# RFID_Sheet_1.net
KiCad netlist of a schematic drawn in Altium Designer
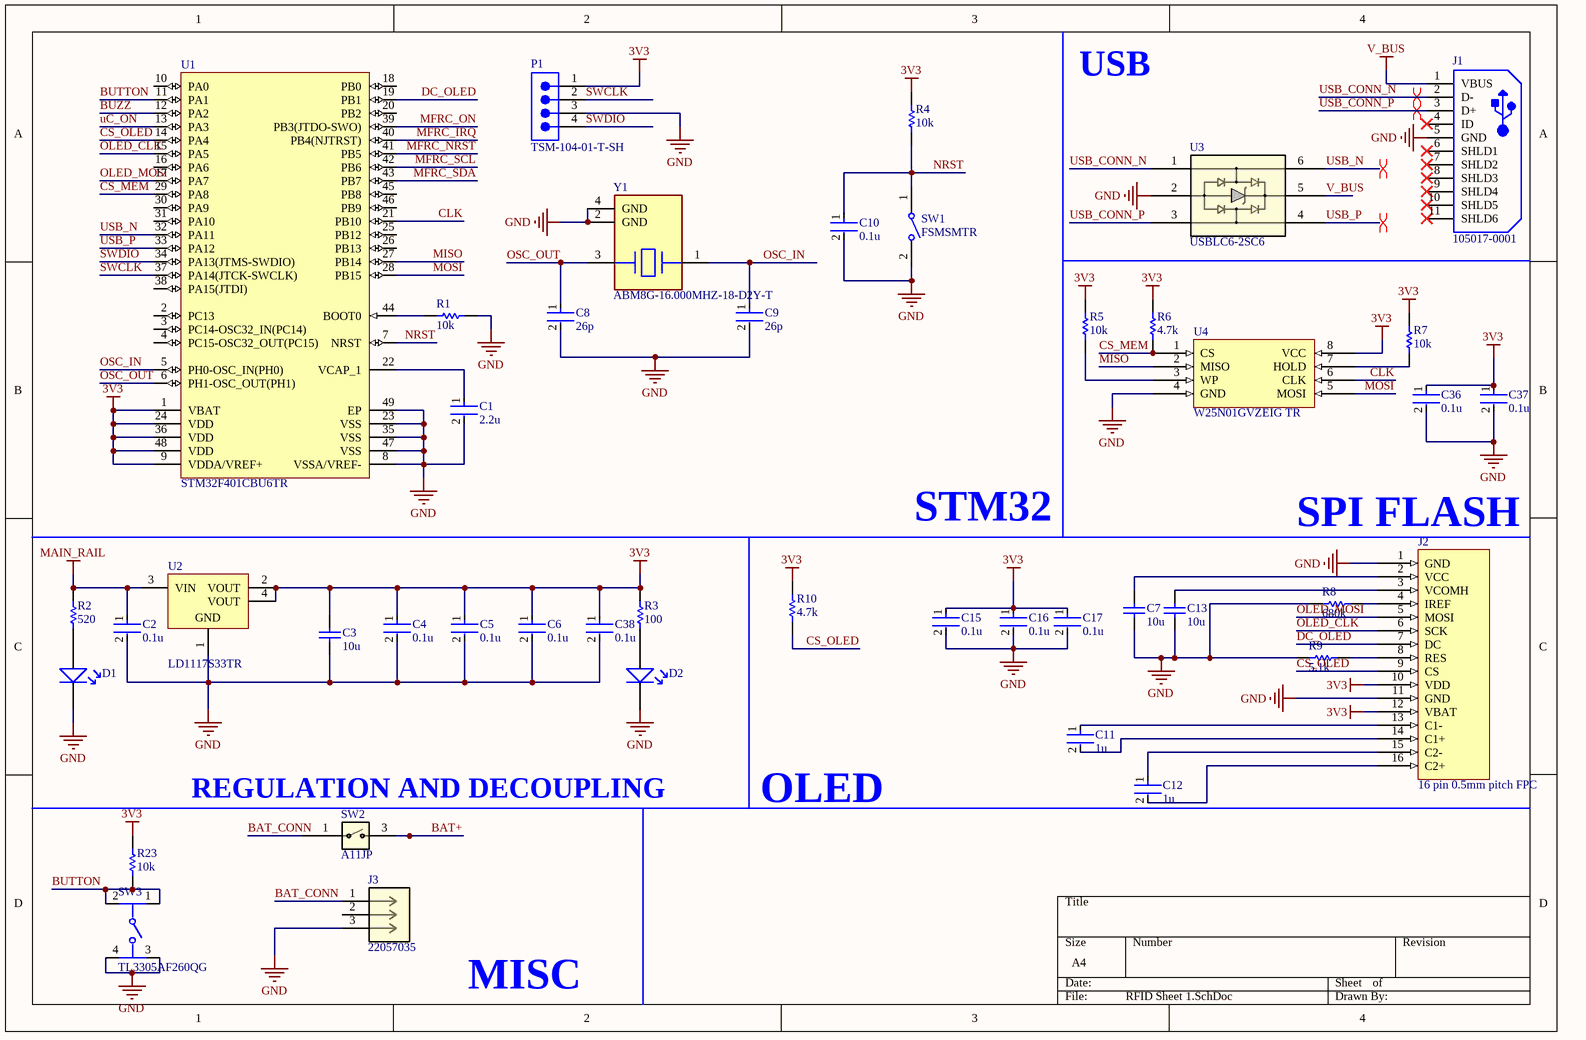
[diagram p0: RFID Sheet 1.SchDoc]

(export (version "E")
  (design (tool "Eeschema 10.0.6"))
  (components
    (comp (ref "C1")
      (value "2.2u")
      (footprint "FP-C0603C-CF-MFG")
      (description "CAP CER 0.1UF 50V X7R 0603")
      (fields (field (name "TOLERANCE") "0.1") (field (name "MANUFACTURER") "KEMET"))
      (libsource (lib "Altium Content Vault") (part "b4654b650e69147ec39a6b967a45e02"))
    )
    (comp (ref "C2")
      (value "0.1u")
      (footprint "FP-C0603C-CF-MFG")
      (description "CAP CER 0.1UF 50V X7R 0603")
      (fields (field (name "TOLERANCE") "0.1") (field (name "MANUFACTURER") "KEMET"))
      (libsource (lib "Altium Content Vault") (part "b4654b650e69147ec39a6b967a45e02"))
    )
    (comp (ref "C3")
      (value "10u")
      (footprint "CAPC2013X88X50LL20T25")
      (fields (field (name "MANUFACTURER") "Kemet") (field (name "PART NUMBER") "C0805C103K5RACTU"))
      (libsource (lib "Altium Content Vault") (part "CAP"))
    )
    (comp (ref "C4")
      (value "0.1u")
      (footprint "FP-C0603C-CF-MFG")
      (description "CAP CER 0.1UF 50V X7R 0603")
      (fields (field (name "TOLERANCE") "0.1") (field (name "MANUFACTURER") "KEMET"))
      (libsource (lib "Altium Content Vault") (part "b4654b650e69147ec39a6b967a45e02"))
    )
    (comp (ref "C5")
      (value "0.1u")
      (footprint "FP-C0603C-CF-MFG")
      (description "CAP CER 0.1UF 50V X7R 0603")
      (fields (field (name "TOLERANCE") "0.1") (field (name "MANUFACTURER") "KEMET"))
      (libsource (lib "Altium Content Vault") (part "b4654b650e69147ec39a6b967a45e02"))
    )
    (comp (ref "C6")
      (value "0.1u")
      (footprint "FP-C0603C-CF-MFG")
      (description "CAP CER 0.1UF 50V X7R 0603")
      (fields (field (name "TOLERANCE") "0.1") (field (name "MANUFACTURER") "KEMET"))
      (libsource (lib "Altium Content Vault") (part "b4654b650e69147ec39a6b967a45e02"))
    )
    (comp (ref "C7")
      (value "10u")
      (footprint "CAPC2013X88X50LL20T25")
      (fields (field (name "MANUFACTURER") "Kemet") (field (name "PART NUMBER") "C0805C103K5RACTU"))
      (libsource (lib "Altium Content Vault") (part "CAP"))
    )
    (comp (ref "C8")
      (value "26p")
      (footprint "FP-C0603C-CF-MFG")
      (description "CAP CER 0.1UF 50V X7R 0603")
      (fields (field (name "TOLERANCE") "0.1") (field (name "MANUFACTURER") "KEMET"))
      (libsource (lib "Altium Content Vault") (part "b4654b650e69147ec39a6b967a45e02"))
    )
    (comp (ref "C9")
      (value "26p")
      (footprint "FP-C0603C-CF-MFG")
      (description "CAP CER 0.1UF 50V X7R 0603")
      (fields (field (name "TOLERANCE") "0.1") (field (name "MANUFACTURER") "KEMET"))
      (libsource (lib "Altium Content Vault") (part "b4654b650e69147ec39a6b967a45e02"))
    )
    (comp (ref "C10")
      (value "0.1u")
      (footprint "FP-C0603C-CF-MFG")
      (description "CAP CER 0.1UF 50V X7R 0603")
      (fields (field (name "TOLERANCE") "0.1") (field (name "MANUFACTURER") "KEMET"))
      (libsource (lib "Altium Content Vault") (part "b4654b650e69147ec39a6b967a45e02"))
    )
    (comp (ref "C11")
      (value "1u")
      (footprint "FP-C0603C-CF-MFG")
      (description "CAP CER 0.1UF 50V X7R 0603")
      (fields (field (name "TOLERANCE") "0.1") (field (name "MANUFACTURER") "KEMET"))
      (libsource (lib "Altium Content Vault") (part "b4654b650e69147ec39a6b967a45e02"))
    )
    (comp (ref "C12")
      (value "1u")
      (footprint "FP-C0603C-CF-MFG")
      (description "CAP CER 0.1UF 50V X7R 0603")
      (fields (field (name "TOLERANCE") "0.1") (field (name "MANUFACTURER") "KEMET"))
      (libsource (lib "Altium Content Vault") (part "b4654b650e69147ec39a6b967a45e02"))
    )
    (comp (ref "C13")
      (value "10u")
      (footprint "CAPC2013X88X50LL20T25")
      (fields (field (name "MANUFACTURER") "Kemet") (field (name "PART NUMBER") "C0805C103K5RACTU"))
      (libsource (lib "Altium Content Vault") (part "CAP"))
    )
    (comp (ref "C15")
      (value "0.1u")
      (footprint "FP-C0603C-CF-MFG")
      (description "CAP CER 0.1UF 50V X7R 0603")
      (fields (field (name "TOLERANCE") "0.1") (field (name "MANUFACTURER") "KEMET"))
      (libsource (lib "Altium Content Vault") (part "b4654b650e69147ec39a6b967a45e02"))
    )
    (comp (ref "C16")
      (value "0.1u")
      (footprint "FP-C0603C-CF-MFG")
      (description "CAP CER 0.1UF 50V X7R 0603")
      (fields (field (name "TOLERANCE") "0.1") (field (name "MANUFACTURER") "KEMET"))
      (libsource (lib "Altium Content Vault") (part "b4654b650e69147ec39a6b967a45e02"))
    )
    (comp (ref "C17")
      (value "0.1u")
      (footprint "FP-C0603C-CF-MFG")
      (description "CAP CER 0.1UF 50V X7R 0603")
      (fields (field (name "TOLERANCE") "0.1") (field (name "MANUFACTURER") "KEMET"))
      (libsource (lib "Altium Content Vault") (part "b4654b650e69147ec39a6b967a45e02"))
    )
    (comp (ref "C36")
      (value "0.1u")
      (footprint "FP-C0603C-CF-MFG")
      (description "CAP CER 0.1UF 50V X7R 0603")
      (fields (field (name "TOLERANCE") "0.1") (field (name "MANUFACTURER") "KEMET"))
      (libsource (lib "Altium Content Vault") (part "b4654b650e69147ec39a6b967a45e02"))
    )
    (comp (ref "C37")
      (value "0.1u")
      (footprint "FP-C0603C-CF-MFG")
      (description "CAP CER 0.1UF 50V X7R 0603")
      (fields (field (name "TOLERANCE") "0.1") (field (name "MANUFACTURER") "KEMET"))
      (libsource (lib "Altium Content Vault") (part "b4654b650e69147ec39a6b967a45e02"))
    )
    (comp (ref "C38")
      (value "0.1u")
      (footprint "FP-C0603C-CF-MFG")
      (description "CAP CER 0.1UF 50V X7R 0603")
      (fields (field (name "TOLERANCE") "0.1") (field (name "MANUFACTURER") "KEMET"))
      (libsource (lib "Altium Content Vault") (part "b4654b650e69147ec39a6b967a45e02"))
    )
    (comp (ref "D1") (value "0603 LED") (footprint "0603 LED") (libsource (lib "0603 LED") (part "0603 LED")))
    (comp (ref "D2") (value "0603 LED") (footprint "0603 LED") (libsource (lib "0603 LED") (part "0603 LED")))
    (comp (ref "J1")
      (value "105017-0001")
      (footprint "USB-MICRO-B_V")
      (fields (field (name "MANUFACTURER") "Molex"))
      (libsource (lib "Altium Content Vault") (part "USB-5-6SHLD"))
    )
    (comp (ref "J2")
      (value "16 pin 0.5mm pitch FPC")
      (footprint "16pin 0.5P FPC")
      (libsource (lib "Master") (part "16 pin 0.5mm pitch FPC"))
    )
    (comp (ref "J3")
      (value "22057035")
      (footprint "CON_22057035_MOL")
      (description "No Description Available")
      (fields (field (name "COPYRIGHT") "Copyright (C) 2024 Ultra Librarian. All rights reserved."))
      (libsource (lib "22057035") (part "22057035"))
    )
    (comp (ref "P1")
      (value "TSM-104-01-T-SH")
      (footprint "SMTC-TSM-104-01-X-SH")
      (fields (field (name "MANUFACTURER") "Samtec"))
      (libsource (lib "Altium Content Vault") (part "SMTC-TSM-104-01-X-SH"))
    )
    (comp (ref "R1")
      (value "10k")
      (footprint "RESC1609X50X30NL8T20")
      (description "Chip Resistor, 10 KOhm, +/- 1%, 100 mW, -55 to 155 degC, 0603 (1608 Metric), RoHS, Tape and Reel")
      (fields (field (name "MANUFACTURER") "Vishay Semiconductor"))
      (libsource (lib "Altium Content Vault") (part "RES-2"))
    )
    (comp (ref "R2")
      (value "520")
      (footprint "RESC1609X50X30NL8T20")
      (description "Chip Resistor, 10 KOhm, +/- 1%, 100 mW, -55 to 155 degC, 0603 (1608 Metric), RoHS, Tape and Reel")
      (fields (field (name "MANUFACTURER") "Vishay Semiconductor"))
      (libsource (lib "Altium Content Vault") (part "RES-2"))
    )
    (comp (ref "R3")
      (value "100")
      (footprint "RESC1609X50X30NL8T20")
      (description "Chip Resistor, 10 KOhm, +/- 1%, 100 mW, -55 to 155 degC, 0603 (1608 Metric), RoHS, Tape and Reel")
      (fields (field (name "MANUFACTURER") "Vishay Semiconductor"))
      (libsource (lib "Altium Content Vault") (part "RES-2"))
    )
    (comp (ref "R4")
      (value "10k")
      (footprint "RESC1609X50X30NL8T20")
      (description "Chip Resistor, 10 KOhm, +/- 1%, 100 mW, -55 to 155 degC, 0603 (1608 Metric), RoHS, Tape and Reel")
      (fields (field (name "MANUFACTURER") "Vishay Semiconductor"))
      (libsource (lib "Altium Content Vault") (part "RES-2"))
    )
    (comp (ref "R5")
      (value "10k")
      (footprint "RESC1609X50X30NL8T20")
      (description "Chip Resistor, 10 KOhm, +/- 1%, 100 mW, -55 to 155 degC, 0603 (1608 Metric), RoHS, Tape and Reel")
      (fields (field (name "MANUFACTURER") "Vishay Semiconductor"))
      (libsource (lib "Altium Content Vault") (part "RES-2"))
    )
    (comp (ref "R6")
      (value "4.7k")
      (footprint "RESC1609X50X30NL8T20")
      (description "Chip Resistor, 10 KOhm, +/- 1%, 100 mW, -55 to 155 degC, 0603 (1608 Metric), RoHS, Tape and Reel")
      (fields (field (name "MANUFACTURER") "Vishay Semiconductor"))
      (libsource (lib "Altium Content Vault") (part "RES-2"))
    )
    (comp (ref "R7")
      (value "10k")
      (footprint "RESC1609X50X30NL8T20")
      (description "Chip Resistor, 10 KOhm, +/- 1%, 100 mW, -55 to 155 degC, 0603 (1608 Metric), RoHS, Tape and Reel")
      (fields (field (name "MANUFACTURER") "Vishay Semiconductor"))
      (libsource (lib "Altium Content Vault") (part "RES-2"))
    )
    (comp (ref "R8")
      (value "680k")
      (footprint "RESC1609X50X30NL8T20")
      (description "Chip Resistor, 10 KOhm, +/- 1%, 100 mW, -55 to 155 degC, 0603 (1608 Metric), RoHS, Tape and Reel")
      (fields (field (name "MANUFACTURER") "Vishay Semiconductor"))
      (libsource (lib "Altium Content Vault") (part "RES-2"))
    )
    (comp (ref "R9")
      (value "5.1k")
      (footprint "RESC1609X50X30NL8T20")
      (description "Chip Resistor, 10 KOhm, +/- 1%, 100 mW, -55 to 155 degC, 0603 (1608 Metric), RoHS, Tape and Reel")
      (fields (field (name "MANUFACTURER") "Vishay Semiconductor"))
      (libsource (lib "Altium Content Vault") (part "RES-2"))
    )
    (comp (ref "R10")
      (value "4.7k")
      (footprint "RESC1609X50X30NL8T20")
      (description "Chip Resistor, 10 KOhm, +/- 1%, 100 mW, -55 to 155 degC, 0603 (1608 Metric), RoHS, Tape and Reel")
      (fields (field (name "MANUFACTURER") "Vishay Semiconductor"))
      (libsource (lib "Altium Content Vault") (part "RES-2"))
    )
    (comp (ref "R23")
      (value "10k")
      (footprint "RESC1609X50X30NL8T20")
      (description "Chip Resistor, 10 KOhm, +/- 1%, 100 mW, -55 to 155 degC, 0603 (1608 Metric), RoHS, Tape and Reel")
      (fields (field (name "MANUFACTURER") "Vishay Semiconductor"))
      (libsource (lib "Altium Content Vault") (part "RES-2"))
    )
    (comp (ref "SW1")
      (value "FSMSMTR")
      (footprint "TECO-FSMSMTR_V")
      (description "FSMSM Push Button Switch, 50 mA, -35 to 85 degC, 2-Pin SMD, RoHS, Tape and Reel")
      (fields (field (name "MANUFACTURER") "TE Connectivity"))
      (libsource (lib "Altium Content Vault") (part "SW-SPST-2_C"))
    )
    (comp (ref "SW2")
      (value "A11JP")
      (footprint "A11JP_NKK")
      (description "No Description Available")
      (fields (field (name "COPYRIGHT") "Copyright (C) 2024 Ultra Librarian. All rights reserved."))
      (libsource (lib "A11JP") (part "A11JP"))
    )
    (comp (ref "SW3")
      (value "TL3305AF260QG")
      (footprint "FP-TL3305AF260QG-MFG")
      (description "SWITCH TACTILE SPST-NO 50MA 12V")
      (libsource (lib "Altium Content Vault") (part "b8895f3f4cefb76e1819d2863dba89b"))
    )
    (comp (ref "U1")
      (value "STM32F401CBU6TR")
      (footprint "STM32F401CBU6")
      (fields (field (name "MANUFACTURER") "STMicroelectronics"))
      (libsource (lib "STM32F401CBU6TR") (part "CMP-0243-00136-1"))
    )
    (comp (ref "U2")
      (value "LD1117S33TR")
      (footprint "SOT230P700X180-4N")
      (description "Fixed Positive LDO Regulator, 3.3V, 1.2V Dropout, BIPolar, PDSO4")
      (fields (field (name "MANUFACTURER") "STMicroelectronics"))
      (libsource (lib "0603 LED") (part "LD1117S33TR"))
    )
    (comp (ref "U3")
      (value "USBLC6-2SC6")
      (footprint "SOT23-6L_STM")
      (description "No Description Available")
      (fields (field (name "COPYRIGHT") "Copyright (C) 2023 Ultra Librarian. All rights reserved."))
      (libsource (lib "USBLC6-2SC6") (part "USBLC6-2SC6"))
    )
    (comp (ref "U4")
      (value "W25N01GVZEIG TR")
      (footprint "W25N01GVZEIG")
      (libsource (lib "Master") (part "W25N01GVZEIG TR"))
    )
    (comp (ref "Y1")
      (value "ABM8G-16.000MHZ-18-D2Y-T")
      (footprint "FP-ABM8G-MFG")
      (description "Crystal 16MHz ±20ppm (Tol) ±30ppm (Stability) 18pF FUND 80Ω 4-Pin SMD T/R")
      (fields (field (name "TOLERANCE") "20ppm"))
      (libsource (lib "Altium Content Vault") (part "48e526d86b7f2615d98721063c72f49"))
    )
  )
  (nets
    (net (code "1") (name "/BAT+") (class "Default")
      (node (ref "SW2") (pin "3") (pinfunction "3_3") (pintype "passive"))
    )
    (net (code "2") (name "/BAT_CONN") (class "Default")
      (node (ref "J3") (pin "1") (pinfunction "1_1") (pintype "passive"))
      (node (ref "SW2") (pin "1") (pinfunction "1_1") (pintype "passive"))
    )
    (net (code "3") (name "/BUTTON") (class "Default")
      (node (ref "R23") (pin "1") (pinfunction "1_1") (pintype "passive"))
      (node (ref "SW3") (pin "1") (pinfunction "1_1") (pintype "passive"))
      (node (ref "SW3") (pin "2") (pinfunction "2_2") (pintype "passive"))
      (node (ref "U1") (pin "11") (pinfunction "PA1_11") (pintype "bidirectional"))
    )
    (net (code "4") (name "/BUZZ") (class "Default")
      (node (ref "U1") (pin "12") (pinfunction "PA2_12") (pintype "bidirectional"))
    )
    (net (code "5") (name "/CLK") (class "Default")
      (node (ref "U1") (pin "21") (pinfunction "PB10_21") (pintype "bidirectional"))
      (node (ref "U4") (pin "6") (pinfunction "CLK_6") (pintype "input"))
    )
    (net (code "6") (name "/CS_MEM") (class "Default")
      (node (ref "R6") (pin "1") (pinfunction "1_1") (pintype "passive"))
      (node (ref "U1") (pin "29") (pinfunction "PA8_29") (pintype "bidirectional"))
      (node (ref "U4") (pin "1") (pinfunction "CS_1") (pintype "input"))
    )
    (net (code "7") (name "/CS_OLED") (class "Default")
      (node (ref "J2") (pin "9") (pinfunction "CS_9") (pintype "input"))
      (node (ref "R10") (pin "1") (pinfunction "1_1") (pintype "passive"))
      (node (ref "U1") (pin "14") (pinfunction "PA4_14") (pintype "bidirectional"))
    )
    (net (code "8") (name "/DC_OLED") (class "Default")
      (node (ref "J2") (pin "7") (pinfunction "DC_7") (pintype "input"))
      (node (ref "U1") (pin "19") (pinfunction "PB1_19") (pintype "bidirectional"))
    )
    (net (code "9") (name "/MFRC_IRQ") (class "Default")
      (node (ref "U1") (pin "40") (pinfunction "PB4(NJTRST)_40") (pintype "bidirectional"))
    )
    (net (code "10") (name "/MFRC_NRST") (class "Default")
      (node (ref "U1") (pin "41") (pinfunction "PB5_41") (pintype "bidirectional"))
    )
    (net (code "11") (name "/MFRC_ON") (class "Default")
      (node (ref "U1") (pin "39") (pinfunction "PB3(JTDO-SWO)_39") (pintype "bidirectional"))
    )
    (net (code "12") (name "/MFRC_SCL") (class "Default")
      (node (ref "U1") (pin "42") (pinfunction "PB6_42") (pintype "bidirectional"))
    )
    (net (code "13") (name "/MFRC_SDA") (class "Default")
      (node (ref "U1") (pin "43") (pinfunction "PB7_43") (pintype "bidirectional"))
    )
    (net (code "14") (name "/MISO") (class "Default")
      (node (ref "U1") (pin "27") (pinfunction "PB14_27") (pintype "bidirectional"))
      (node (ref "U4") (pin "2") (pinfunction "MISO_2") (pintype "input"))
    )
    (net (code "15") (name "/MOSI") (class "Default")
      (node (ref "U1") (pin "28") (pinfunction "PB15_28") (pintype "bidirectional"))
      (node (ref "U4") (pin "5") (pinfunction "MOSI_5") (pintype "input"))
    )
    (net (code "16") (name "/NRST") (class "Default")
      (node (ref "C10") (pin "1") (pinfunction "1_1") (pintype "passive"))
      (node (ref "R4") (pin "2") (pinfunction "2_2") (pintype "passive"))
      (node (ref "SW1") (pin "1") (pinfunction "1_1") (pintype "passive"))
      (node (ref "U1") (pin "7") (pinfunction "NRST_7") (pintype "bidirectional"))
    )
    (net (code "17") (name "/OLED_CLK") (class "Default")
      (node (ref "J2") (pin "6") (pinfunction "SCK_6") (pintype "input"))
      (node (ref "U1") (pin "15") (pinfunction "PA5_15") (pintype "bidirectional"))
    )
    (net (code "18") (name "/OLED_MOSI") (class "Default")
      (node (ref "J2") (pin "5") (pinfunction "MOSI_5") (pintype "input"))
      (node (ref "U1") (pin "17") (pinfunction "PA7_17") (pintype "bidirectional"))
    )
    (net (code "19") (name "/OSC_IN") (class "Default")
      (node (ref "C9") (pin "1") (pinfunction "1_1") (pintype "passive"))
      (node (ref "U1") (pin "5") (pinfunction "PH0-OSC_IN(PH0)_5") (pintype "bidirectional"))
      (node (ref "Y1") (pin "1") (pinfunction "1_1") (pintype "passive"))
    )
    (net (code "20") (name "/OSC_OUT") (class "Default")
      (node (ref "C8") (pin "1") (pinfunction "1_1") (pintype "passive"))
      (node (ref "U1") (pin "6") (pinfunction "PH1-OSC_OUT(PH1)_6") (pintype "bidirectional"))
      (node (ref "Y1") (pin "3") (pinfunction "3_3") (pintype "passive"))
    )
    (net (code "21") (name "/SWCLK") (class "Default")
      (node (ref "P1") (pin "2") (pinfunction "2_2") (pintype "passive"))
      (node (ref "U1") (pin "37") (pinfunction "PA14(JTCK-SWCLK)_37") (pintype "bidirectional"))
    )
    (net (code "22") (name "/SWDIO") (class "Default")
      (node (ref "P1") (pin "4") (pinfunction "4_4") (pintype "passive"))
      (node (ref "U1") (pin "34") (pinfunction "PA13(JTMS-SWDIO)_34") (pintype "bidirectional"))
    )
    (net (code "23") (name "/USB_CONN_N") (class "Default")
      (node (ref "J1") (pin "2") (pinfunction "D-_2") (pintype "passive"))
      (node (ref "U3") (pin "1") (pinfunction "1_1") (pintype "passive"))
    )
    (net (code "24") (name "/USB_CONN_P") (class "Default")
      (node (ref "J1") (pin "3") (pinfunction "D+_3") (pintype "passive"))
      (node (ref "U3") (pin "3") (pinfunction "3_3") (pintype "passive"))
    )
    (net (code "25") (name "/USB_N") (class "Default")
      (node (ref "U1") (pin "32") (pinfunction "PA11_32") (pintype "bidirectional"))
      (node (ref "U3") (pin "6") (pinfunction "6_6") (pintype "passive"))
    )
    (net (code "26") (name "/USB_P") (class "Default")
      (node (ref "U1") (pin "33") (pinfunction "PA12_33") (pintype "bidirectional"))
      (node (ref "U3") (pin "4") (pinfunction "4_4") (pintype "passive"))
    )
    (net (code "27") (name "/uC_ON") (class "Default")
      (node (ref "U1") (pin "13") (pinfunction "PA3_13") (pintype "bidirectional"))
    )
    (net (code "28") (name "3V3") (class "Default")
      (node (ref "C15") (pin "1") (pinfunction "1_1") (pintype "passive"))
      (node (ref "C16") (pin "1") (pinfunction "1_1") (pintype "passive"))
      (node (ref "C17") (pin "1") (pinfunction "1_1") (pintype "passive"))
      (node (ref "C3") (pin "2") (pinfunction "2_2") (pintype "passive"))
      (node (ref "C36") (pin "1") (pinfunction "1_1") (pintype "passive"))
      (node (ref "C37") (pin "1") (pinfunction "1_1") (pintype "passive"))
      (node (ref "C38") (pin "1") (pinfunction "1_1") (pintype "passive"))
      (node (ref "C4") (pin "1") (pinfunction "1_1") (pintype "passive"))
      (node (ref "C5") (pin "1") (pinfunction "1_1") (pintype "passive"))
      (node (ref "C6") (pin "1") (pinfunction "1_1") (pintype "passive"))
      (node (ref "J2") (pin "10") (pinfunction "VDD_10") (pintype "input"))
      (node (ref "J2") (pin "12") (pinfunction "VBAT_12") (pintype "input"))
      (node (ref "P1") (pin "1") (pinfunction "1_1") (pintype "passive"))
      (node (ref "R10") (pin "2") (pinfunction "2_2") (pintype "passive"))
      (node (ref "R23") (pin "2") (pinfunction "2_2") (pintype "passive"))
      (node (ref "R3") (pin "2") (pinfunction "2_2") (pintype "passive"))
      (node (ref "R4") (pin "1") (pinfunction "1_1") (pintype "passive"))
      (node (ref "R5") (pin "2") (pinfunction "2_2") (pintype "passive"))
      (node (ref "R6") (pin "2") (pinfunction "2_2") (pintype "passive"))
      (node (ref "R7") (pin "2") (pinfunction "2_2") (pintype "passive"))
      (node (ref "U1") (pin "1") (pinfunction "VBAT_1") (pintype "power_in"))
      (node (ref "U1") (pin "24") (pinfunction "VDD_24") (pintype "power_in"))
      (node (ref "U1") (pin "36") (pinfunction "VDD_36") (pintype "power_in"))
      (node (ref "U1") (pin "48") (pinfunction "VDD_48") (pintype "power_in"))
      (node (ref "U1") (pin "9") (pinfunction "VDDA/VREF+_9") (pintype "power_in"))
      (node (ref "U2") (pin "2") (pinfunction "VOUT_2") (pintype "power_in"))
      (node (ref "U2") (pin "4") (pinfunction "VOUT_4") (pintype "power_in"))
      (node (ref "U4") (pin "8") (pinfunction "VCC_8") (pintype "input"))
    )
    (net (code "29") (name "GND") (class "Default")
      (node (ref "C1") (pin "2") (pinfunction "2_2") (pintype "passive"))
      (node (ref "C10") (pin "2") (pinfunction "2_2") (pintype "passive"))
      (node (ref "C13") (pin "1") (pinfunction "1_1") (pintype "passive"))
      (node (ref "C15") (pin "2") (pinfunction "2_2") (pintype "passive"))
      (node (ref "C16") (pin "2") (pinfunction "2_2") (pintype "passive"))
      (node (ref "C17") (pin "2") (pinfunction "2_2") (pintype "passive"))
      (node (ref "C2") (pin "2") (pinfunction "2_2") (pintype "passive"))
      (node (ref "C3") (pin "1") (pinfunction "1_1") (pintype "passive"))
      (node (ref "C36") (pin "2") (pinfunction "2_2") (pintype "passive"))
      (node (ref "C37") (pin "2") (pinfunction "2_2") (pintype "passive"))
      (node (ref "C38") (pin "2") (pinfunction "2_2") (pintype "passive"))
      (node (ref "C4") (pin "2") (pinfunction "2_2") (pintype "passive"))
      (node (ref "C5") (pin "2") (pinfunction "2_2") (pintype "passive"))
      (node (ref "C6") (pin "2") (pinfunction "2_2") (pintype "passive"))
      (node (ref "C7") (pin "1") (pinfunction "1_1") (pintype "passive"))
      (node (ref "C8") (pin "2") (pinfunction "2_2") (pintype "passive"))
      (node (ref "C9") (pin "2") (pinfunction "2_2") (pintype "passive"))
      (node (ref "D1") (pin "2") (pinfunction "5_2") (pintype "passive"))
      (node (ref "D2") (pin "2") (pinfunction "5_2") (pintype "passive"))
      (node (ref "J1") (pin "5") (pinfunction "GND_5") (pintype "passive"))
      (node (ref "J2") (pin "1") (pinfunction "GND_1") (pintype "input"))
      (node (ref "J2") (pin "11") (pinfunction "GND_11") (pintype "input"))
      (node (ref "J3") (pin "3") (pinfunction "3_3") (pintype "passive"))
      (node (ref "P1") (pin "3") (pinfunction "3_3") (pintype "passive"))
      (node (ref "R1") (pin "2") (pinfunction "2_2") (pintype "passive"))
      (node (ref "R8") (pin "2") (pinfunction "2_2") (pintype "passive"))
      (node (ref "R9") (pin "2") (pinfunction "2_2") (pintype "passive"))
      (node (ref "SW1") (pin "2") (pinfunction "2_2") (pintype "passive"))
      (node (ref "SW3") (pin "3") (pinfunction "3_3") (pintype "passive"))
      (node (ref "SW3") (pin "4") (pinfunction "4_4") (pintype "passive"))
      (node (ref "U1") (pin "23") (pinfunction "VSS_23") (pintype "power_in"))
      (node (ref "U1") (pin "35") (pinfunction "VSS_35") (pintype "power_in"))
      (node (ref "U1") (pin "47") (pinfunction "VSS_47") (pintype "power_in"))
      (node (ref "U1") (pin "49") (pinfunction "EP_49") (pintype "power_in"))
      (node (ref "U1") (pin "8") (pinfunction "VSSA/VREF-_8") (pintype "power_in"))
      (node (ref "U2") (pin "1") (pinfunction "GND_1") (pintype "power_in"))
      (node (ref "U3") (pin "2") (pinfunction "2_2") (pintype "passive"))
      (node (ref "U4") (pin "4") (pinfunction "GND_4") (pintype "input"))
      (node (ref "Y1") (pin "2") (pinfunction "GND_2") (pintype "power_in"))
      (node (ref "Y1") (pin "4") (pinfunction "GND_4") (pintype "power_in"))
    )
    (net (code "30") (name "MAIN_RAIL") (class "Default")
      (node (ref "C2") (pin "1") (pinfunction "1_1") (pintype "passive"))
      (node (ref "R2") (pin "2") (pinfunction "2_2") (pintype "passive"))
      (node (ref "U2") (pin "3") (pinfunction "VIN_3") (pintype "power_in"))
    )
    (net (code "31") (name "Net-(D1-6)") (class "Default")
      (node (ref "D1") (pin "1") (pinfunction "6_1") (pintype "passive"))
      (node (ref "R2") (pin "1") (pinfunction "1_1") (pintype "passive"))
    )
    (net (code "32") (name "Net-(D2-6)") (class "Default")
      (node (ref "D2") (pin "1") (pinfunction "6_1") (pintype "passive"))
      (node (ref "R3") (pin "1") (pinfunction "1_1") (pintype "passive"))
    )
    (net (code "33") (name "Net-(J2-C1+)") (class "Default")
      (node (ref "C11") (pin "2") (pinfunction "2_2") (pintype "passive"))
      (node (ref "J2") (pin "14") (pinfunction "C1+_14") (pintype "input"))
    )
    (net (code "34") (name "Net-(J2-C1-)") (class "Default")
      (node (ref "C11") (pin "1") (pinfunction "1_1") (pintype "passive"))
      (node (ref "J2") (pin "13") (pinfunction "C1-_13") (pintype "input"))
    )
    (net (code "35") (name "Net-(J2-C2+)") (class "Default")
      (node (ref "C12") (pin "2") (pinfunction "2_2") (pintype "passive"))
      (node (ref "J2") (pin "16") (pinfunction "C2+_16") (pintype "input"))
    )
    (net (code "36") (name "Net-(J2-C2-)") (class "Default")
      (node (ref "C12") (pin "1") (pinfunction "1_1") (pintype "passive"))
      (node (ref "J2") (pin "15") (pinfunction "C2-_15") (pintype "input"))
    )
    (net (code "37") (name "Net-(J2-IREF)") (class "Default")
      (node (ref "J2") (pin "4") (pinfunction "IREF_4") (pintype "input"))
      (node (ref "R8") (pin "1") (pinfunction "1_1") (pintype "passive"))
    )
    (net (code "38") (name "Net-(J2-RES)") (class "Default")
      (node (ref "J2") (pin "8") (pinfunction "RES_8") (pintype "input"))
      (node (ref "R9") (pin "1") (pinfunction "1_1") (pintype "passive"))
    )
    (net (code "39") (name "Net-(J2-VCC)") (class "Default")
      (node (ref "C7") (pin "2") (pinfunction "2_2") (pintype "passive"))
      (node (ref "J2") (pin "2") (pinfunction "VCC_2") (pintype "input"))
    )
    (net (code "40") (name "Net-(J2-VCOMH)") (class "Default")
      (node (ref "C13") (pin "2") (pinfunction "2_2") (pintype "passive"))
      (node (ref "J2") (pin "3") (pinfunction "VCOMH_3") (pintype "input"))
    )
    (net (code "41") (name "Net-(U1-BOOT0)") (class "Default")
      (node (ref "R1") (pin "1") (pinfunction "1_1") (pintype "passive"))
      (node (ref "U1") (pin "44") (pinfunction "BOOT0_44") (pintype "input"))
    )
    (net (code "42") (name "Net-(U1-VCAP_1)") (class "Default")
      (node (ref "C1") (pin "1") (pinfunction "1_1") (pintype "passive"))
      (node (ref "U1") (pin "22") (pinfunction "VCAP_1_22") (pintype "passive"))
    )
    (net (code "43") (name "Net-(U4-HOLD)") (class "Default")
      (node (ref "R7") (pin "1") (pinfunction "1_1") (pintype "passive"))
      (node (ref "U4") (pin "7") (pinfunction "HOLD_7") (pintype "input"))
    )
    (net (code "44") (name "Net-(U4-WP)") (class "Default")
      (node (ref "R5") (pin "1") (pinfunction "1_1") (pintype "passive"))
      (node (ref "U4") (pin "3") (pinfunction "WP_3") (pintype "input"))
    )
    (net (code "45") (name "V_BUS") (class "Default")
      (node (ref "J1") (pin "1") (pinfunction "VBUS_1") (pintype "passive"))
      (node (ref "U3") (pin "5") (pinfunction "5_5") (pintype "passive"))
    )
    (net (code "46") (name "unconnected-(J1-ID-Pad4)") (class "Default")
      (node (ref "J1") (pin "4") (pinfunction "ID_4") (pintype "passive+no_connect"))
    )
    (net (code "47") (name "unconnected-(J1-SHLD1-Pad6)") (class "Default")
      (node (ref "J1") (pin "6") (pinfunction "SHLD1_6") (pintype "passive+no_connect"))
    )
    (net (code "48") (name "unconnected-(J1-SHLD2-Pad7)") (class "Default")
      (node (ref "J1") (pin "7") (pinfunction "SHLD2_7") (pintype "passive+no_connect"))
    )
    (net (code "49") (name "unconnected-(J1-SHLD3-Pad8)") (class "Default")
      (node (ref "J1") (pin "8") (pinfunction "SHLD3_8") (pintype "passive+no_connect"))
    )
    (net (code "50") (name "unconnected-(J1-SHLD4-Pad9)") (class "Default")
      (node (ref "J1") (pin "9") (pinfunction "SHLD4_9") (pintype "passive+no_connect"))
    )
    (net (code "51") (name "unconnected-(J1-SHLD5-Pad10)") (class "Default")
      (node (ref "J1") (pin "10") (pinfunction "SHLD5_10") (pintype "passive+no_connect"))
    )
    (net (code "52") (name "unconnected-(J1-SHLD6-Pad11)") (class "Default")
      (node (ref "J1") (pin "11") (pinfunction "SHLD6_11") (pintype "passive+no_connect"))
    )
    (net (code "53") (name "unconnected-(J3-Pad2)") (class "Default")
      (node (ref "J3") (pin "2") (pinfunction "2_2") (pintype "passive"))
    )
    (net (code "54") (name "unconnected-(U1-PA0-Pad10)") (class "Default")
      (node (ref "U1") (pin "10") (pinfunction "PA0_10") (pintype "bidirectional"))
    )
    (net (code "55") (name "unconnected-(U1-PA6-Pad16)") (class "Default")
      (node (ref "U1") (pin "16") (pinfunction "PA6_16") (pintype "bidirectional"))
    )
    (net (code "56") (name "unconnected-(U1-PA9-Pad30)") (class "Default")
      (node (ref "U1") (pin "30") (pinfunction "PA9_30") (pintype "bidirectional"))
    )
    (net (code "57") (name "unconnected-(U1-PA10-Pad31)") (class "Default")
      (node (ref "U1") (pin "31") (pinfunction "PA10_31") (pintype "bidirectional"))
    )
    (net (code "58") (name "unconnected-(U1-PA15(JTDI)-Pad38)") (class "Default")
      (node (ref "U1") (pin "38") (pinfunction "PA15(JTDI)_38") (pintype "bidirectional"))
    )
    (net (code "59") (name "unconnected-(U1-PB0-Pad18)") (class "Default")
      (node (ref "U1") (pin "18") (pinfunction "PB0_18") (pintype "bidirectional"))
    )
    (net (code "60") (name "unconnected-(U1-PB2-Pad20)") (class "Default")
      (node (ref "U1") (pin "20") (pinfunction "PB2_20") (pintype "bidirectional"))
    )
    (net (code "61") (name "unconnected-(U1-PB8-Pad45)") (class "Default")
      (node (ref "U1") (pin "45") (pinfunction "PB8_45") (pintype "bidirectional"))
    )
    (net (code "62") (name "unconnected-(U1-PB9-Pad46)") (class "Default")
      (node (ref "U1") (pin "46") (pinfunction "PB9_46") (pintype "bidirectional"))
    )
    (net (code "63") (name "unconnected-(U1-PB12-Pad25)") (class "Default")
      (node (ref "U1") (pin "25") (pinfunction "PB12_25") (pintype "bidirectional"))
    )
    (net (code "64") (name "unconnected-(U1-PB13-Pad26)") (class "Default")
      (node (ref "U1") (pin "26") (pinfunction "PB13_26") (pintype "bidirectional"))
    )
    (net (code "65") (name "unconnected-(U1-PC13-Pad2)") (class "Default")
      (node (ref "U1") (pin "2") (pinfunction "PC13_2") (pintype "bidirectional"))
    )
    (net (code "66") (name "unconnected-(U1-PC14-OSC32_IN(PC14)-Pad3)") (class "Default")
      (node (ref "U1") (pin "3") (pinfunction "PC14-OSC32_IN(PC14)_3") (pintype "bidirectional"))
    )
    (net (code "67") (name "unconnected-(U1-PC15-OSC32_OUT(PC15)-Pad4)") (class "Default")
      (node (ref "U1") (pin "4") (pinfunction "PC15-OSC32_OUT(PC15)_4") (pintype "bidirectional"))
    )
  )
)
